# RHB0032E_pac.net
KiCad netlist of a schematic drawn in EAGLE
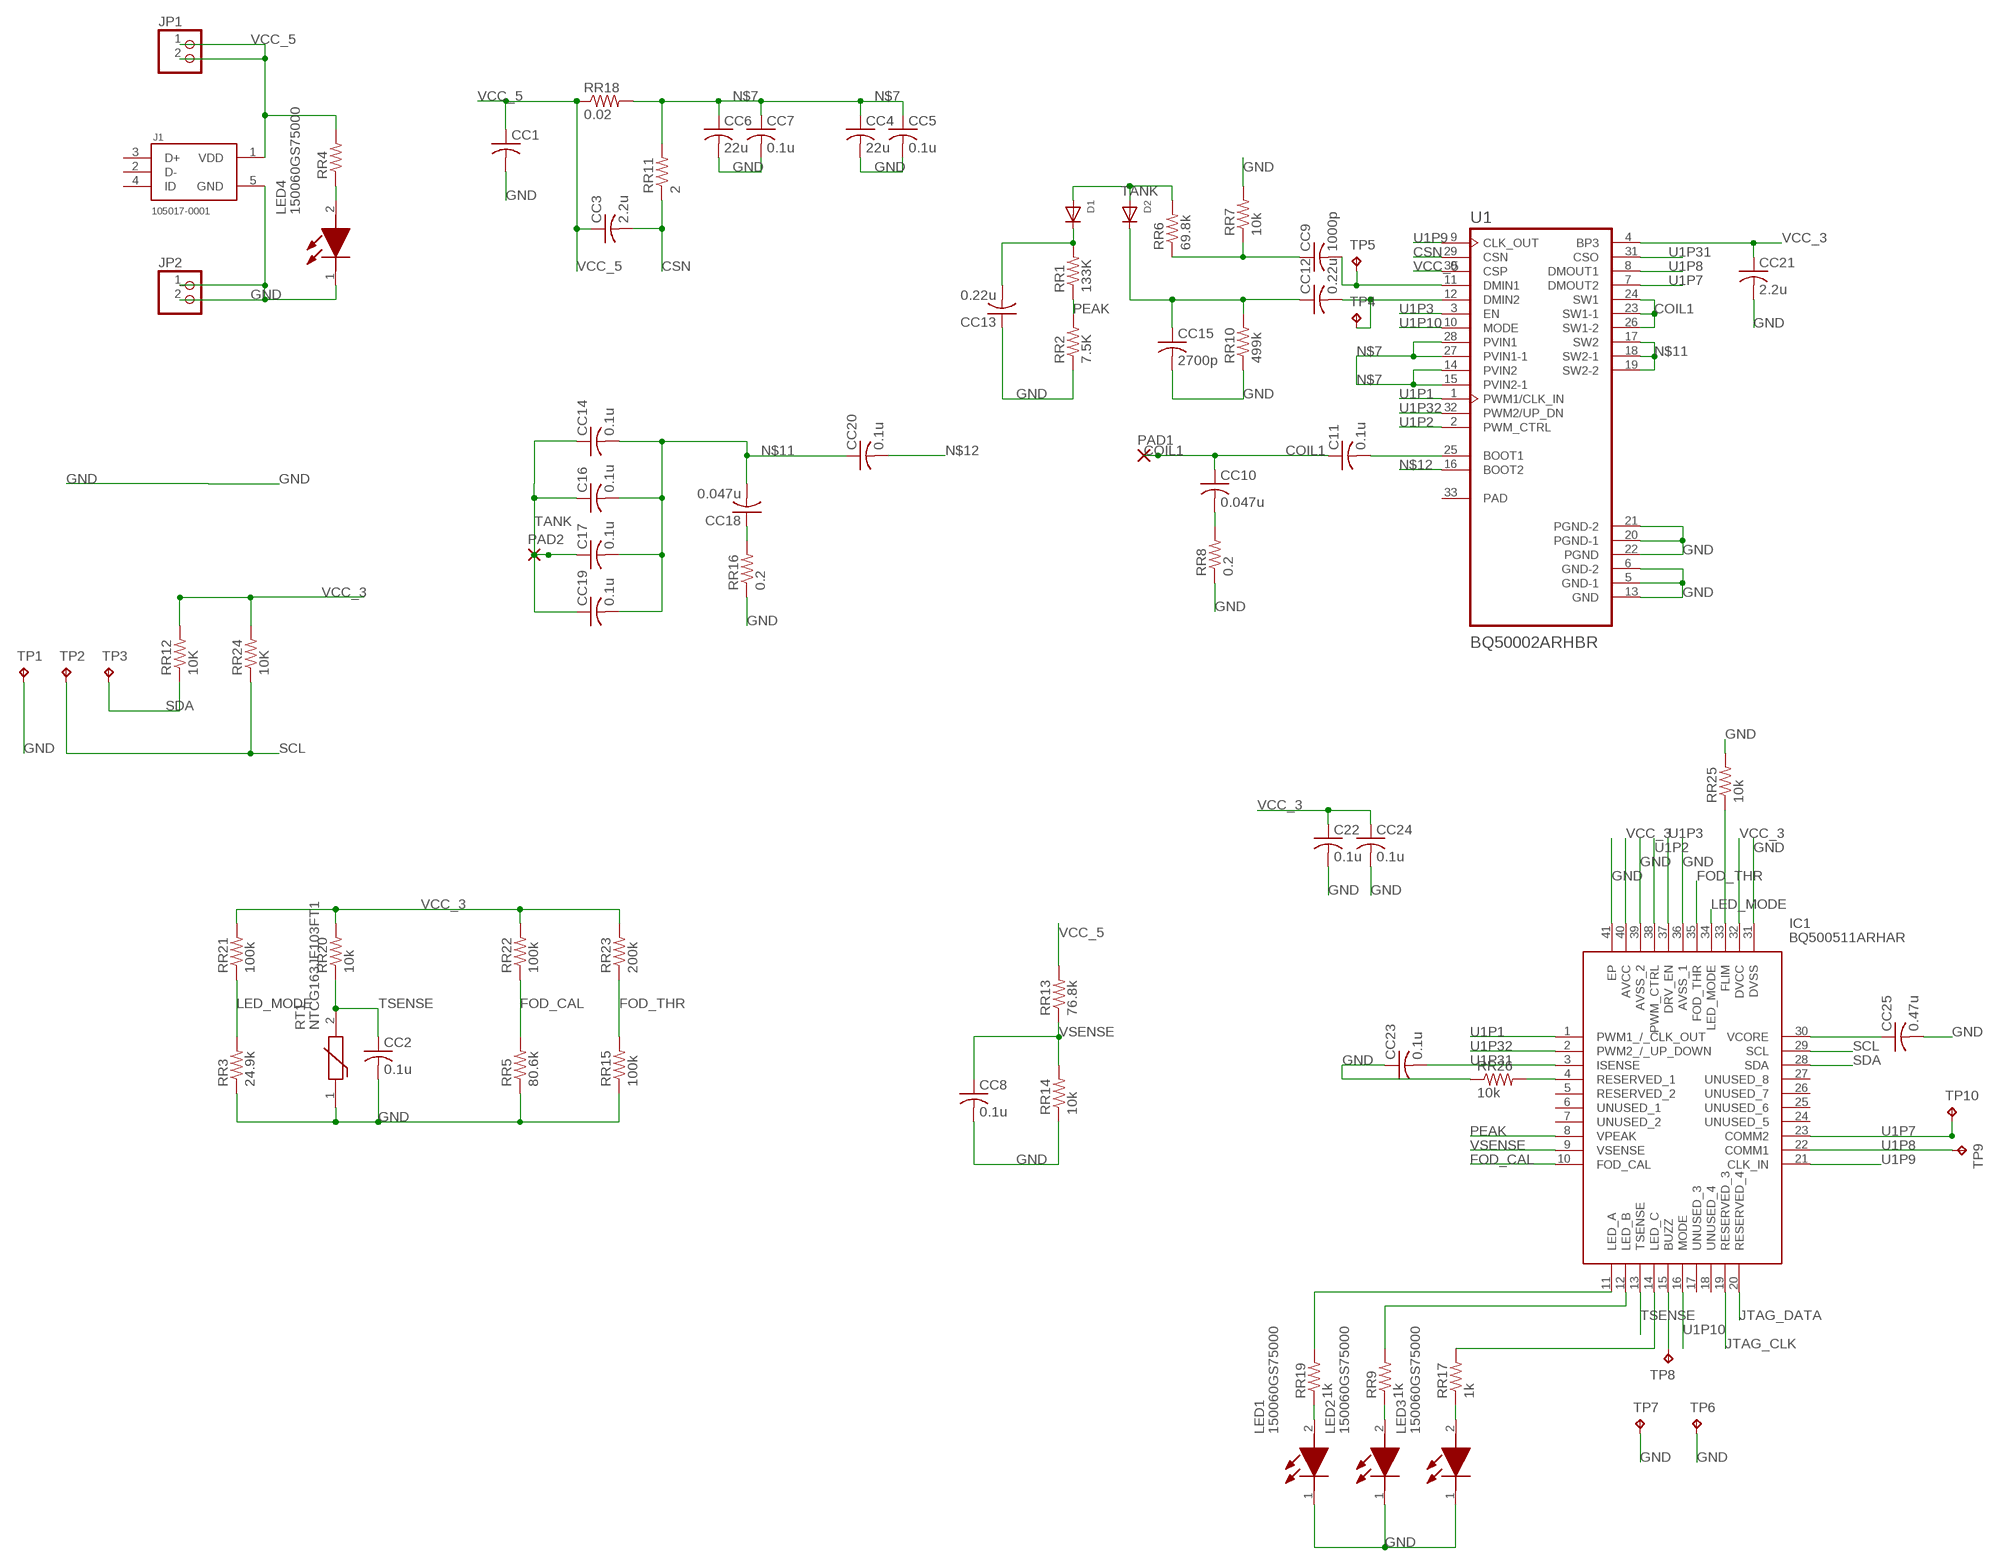
[diagram p0: schematic, sheet 1]

(export (version "E")
  (design (tool "Eeschema 10.0.6"))
  (components
    (comp (ref "C11")
      (value "0.1u")
      (footprint "eagle-import:C0402")
      (libsource (lib "eagle-import") (part "C-USC0402"))
    )
    (comp (ref "C16")
      (value "0.1u")
      (footprint "eagle-import:C0402")
      (libsource (lib "eagle-import") (part "C-USC0402"))
    )
    (comp (ref "C17")
      (value "0.1u")
      (footprint "eagle-import:C0402")
      (libsource (lib "eagle-import") (part "C-USC0402"))
    )
    (comp (ref "C22")
      (value "0.1u")
      (footprint "eagle-import:C0402")
      (libsource (lib "eagle-import") (part "C-USC0402"))
    )
    (comp (ref "CC1")
      (value "C-USC0402")
      (footprint "eagle-import:C0402")
      (libsource (lib "eagle-import") (part "C-USC0402"))
    )
    (comp (ref "CC2")
      (value "0.1u")
      (footprint "eagle-import:C0402")
      (libsource (lib "eagle-import") (part "C-USC0402"))
    )
    (comp (ref "CC3")
      (value "2.2u")
      (footprint "eagle-import:C0402")
      (libsource (lib "eagle-import") (part "C-USC0402"))
    )
    (comp (ref "CC4")
      (value "22u")
      (footprint "eagle-import:C0402")
      (libsource (lib "eagle-import") (part "C-USC0402"))
    )
    (comp (ref "CC5")
      (value "0.1u")
      (footprint "eagle-import:C0402")
      (libsource (lib "eagle-import") (part "C-USC0402"))
    )
    (comp (ref "CC6")
      (value "22u")
      (footprint "eagle-import:C0402")
      (libsource (lib "eagle-import") (part "C-USC0402"))
    )
    (comp (ref "CC7")
      (value "0.1u")
      (footprint "eagle-import:C0402")
      (libsource (lib "eagle-import") (part "C-USC0402"))
    )
    (comp (ref "CC8")
      (value "0.1u")
      (footprint "eagle-import:C0402")
      (libsource (lib "eagle-import") (part "C-USC0402"))
    )
    (comp (ref "CC9")
      (value "1000p")
      (footprint "eagle-import:C0402")
      (libsource (lib "eagle-import") (part "C-USC0402"))
    )
    (comp (ref "CC10")
      (value "0.047u")
      (footprint "eagle-import:C0402")
      (libsource (lib "eagle-import") (part "C-USC0402"))
    )
    (comp (ref "CC12")
      (value "0.22u")
      (footprint "eagle-import:C0402")
      (libsource (lib "eagle-import") (part "C-USC0402"))
    )
    (comp (ref "CC13")
      (value "0.22u")
      (footprint "eagle-import:C0402")
      (libsource (lib "eagle-import") (part "C-USC0402"))
    )
    (comp (ref "CC14")
      (value "0.1u")
      (footprint "eagle-import:C0402")
      (libsource (lib "eagle-import") (part "C-USC0402"))
    )
    (comp (ref "CC15")
      (value "2700p")
      (footprint "eagle-import:C0402")
      (libsource (lib "eagle-import") (part "C-USC0402"))
    )
    (comp (ref "CC18")
      (value "0.047u")
      (footprint "eagle-import:C0402")
      (libsource (lib "eagle-import") (part "C-USC0402"))
    )
    (comp (ref "CC19")
      (value "0.1u")
      (footprint "eagle-import:C0402")
      (libsource (lib "eagle-import") (part "C-USC0402"))
    )
    (comp (ref "CC20")
      (value "0.1u")
      (footprint "eagle-import:C0402")
      (libsource (lib "eagle-import") (part "C-USC0402"))
    )
    (comp (ref "CC21")
      (value "2.2u")
      (footprint "eagle-import:C0402")
      (libsource (lib "eagle-import") (part "C-USC0402"))
    )
    (comp (ref "CC23")
      (value "0.1u")
      (footprint "eagle-import:C0402")
      (libsource (lib "eagle-import") (part "C-USC0402"))
    )
    (comp (ref "CC24")
      (value "0.1u")
      (footprint "eagle-import:C0402")
      (libsource (lib "eagle-import") (part "C-USC0402"))
    )
    (comp (ref "CC25")
      (value "0.47u")
      (footprint "eagle-import:C0402")
      (libsource (lib "eagle-import") (part "C-USC0402"))
    )
    (comp (ref "D1")
      (value "DIODESOD-523")
      (footprint "eagle-import:SOD-523")
      (libsource (lib "eagle-import") (part "DIODESOD-523"))
    )
    (comp (ref "D2")
      (value "DIODESOD-523")
      (footprint "eagle-import:SOD-523")
      (libsource (lib "eagle-import") (part "DIODESOD-523"))
    )
    (comp (ref "IC1")
      (value "BQ500511ARHAR")
      (footprint "eagle-import:QFN50P600X600X100-41N")
      (fields (field (name "MOUSER_PART_NUMBER") "595-BQ500511ARHAR"))
      (libsource (lib "eagle-import") (part "BQ500511ARHAR"))
    )
    (comp (ref "J1")
      (value "105017-0001")
      (footprint "eagle-import:MOLEX_105017-0001")
      (fields (field (name "MF") "Molex"))
      (libsource (lib "eagle-import") (part "105017-0001"))
    )
    (comp (ref "JP1")
      (value "PINHD-1X2")
      (footprint "eagle-import:1X02")
      (libsource (lib "eagle-import") (part "PINHD-1X2"))
    )
    (comp (ref "JP2")
      (value "PINHD-1X2")
      (footprint "eagle-import:1X02")
      (libsource (lib "eagle-import") (part "PINHD-1X2"))
    )
    (comp (ref "LED1")
      (value "150060GS75000")
      (footprint "eagle-import:LEDC1608X80N")
      (fields (field (name "MOUSER_PART_NUMBER") "710-150060GS75000"))
      (libsource (lib "eagle-import") (part "150060GS75000"))
    )
    (comp (ref "LED2")
      (value "150060GS75000")
      (footprint "eagle-import:LEDC1608X80N")
      (fields (field (name "MOUSER_PART_NUMBER") "710-150060GS75000"))
      (libsource (lib "eagle-import") (part "150060GS75000"))
    )
    (comp (ref "LED3")
      (value "150060GS75000")
      (footprint "eagle-import:LEDC1608X80N")
      (fields (field (name "MOUSER_PART_NUMBER") "710-150060GS75000"))
      (libsource (lib "eagle-import") (part "150060GS75000"))
    )
    (comp (ref "LED4")
      (value "150060GS75000")
      (footprint "eagle-import:LEDC1608X80N")
      (fields (field (name "MOUSER_PART_NUMBER") "710-150060GS75000"))
      (libsource (lib "eagle-import") (part "150060GS75000"))
    )
    (comp (ref "PAD1")
      (value "SMD2")
      (footprint "eagle-import:SMD1,27-2,54")
      (libsource (lib "eagle-import") (part "SMD2"))
    )
    (comp (ref "PAD2")
      (value "SMD2")
      (footprint "eagle-import:SMD1,27-2,54")
      (libsource (lib "eagle-import") (part "SMD2"))
    )
    (comp (ref "RR1")
      (value "133K")
      (footprint "eagle-import:R0603")
      (libsource (lib "eagle-import") (part "R-US_R0603"))
    )
    (comp (ref "RR2")
      (value "7.5K")
      (footprint "eagle-import:R0603")
      (libsource (lib "eagle-import") (part "R-US_R0603"))
    )
    (comp (ref "RR3")
      (value "24.9k")
      (footprint "eagle-import:R0603")
      (libsource (lib "eagle-import") (part "R-US_R0603"))
    )
    (comp (ref "RR4")
      (value "R-US_R0603")
      (footprint "eagle-import:R0603")
      (libsource (lib "eagle-import") (part "R-US_R0603"))
    )
    (comp (ref "RR5")
      (value "80.6k")
      (footprint "eagle-import:R0603")
      (libsource (lib "eagle-import") (part "R-US_R0603"))
    )
    (comp (ref "RR6")
      (value "69.8k")
      (footprint "eagle-import:R0603")
      (libsource (lib "eagle-import") (part "R-US_R0603"))
    )
    (comp (ref "RR7")
      (value "10k")
      (footprint "eagle-import:R0603")
      (libsource (lib "eagle-import") (part "R-US_R0603"))
    )
    (comp (ref "RR8")
      (value "0.2")
      (footprint "eagle-import:R0603")
      (libsource (lib "eagle-import") (part "R-US_R0603"))
    )
    (comp (ref "RR9")
      (value "1k")
      (footprint "eagle-import:R0603")
      (libsource (lib "eagle-import") (part "R-US_R0603"))
    )
    (comp (ref "RR10")
      (value "499k")
      (footprint "eagle-import:R0603")
      (libsource (lib "eagle-import") (part "R-US_R0603"))
    )
    (comp (ref "RR11")
      (value "2")
      (footprint "eagle-import:R0603")
      (libsource (lib "eagle-import") (part "R-US_R0603"))
    )
    (comp (ref "RR12")
      (value "10K")
      (footprint "eagle-import:R0603")
      (libsource (lib "eagle-import") (part "R-US_R0603"))
    )
    (comp (ref "RR13")
      (value "76.8k")
      (footprint "eagle-import:R0603")
      (libsource (lib "eagle-import") (part "R-US_R0603"))
    )
    (comp (ref "RR14")
      (value "10k")
      (footprint "eagle-import:R0603")
      (libsource (lib "eagle-import") (part "R-US_R0603"))
    )
    (comp (ref "RR15")
      (value "100k")
      (footprint "eagle-import:R0603")
      (libsource (lib "eagle-import") (part "R-US_R0603"))
    )
    (comp (ref "RR16")
      (value "0.2")
      (footprint "eagle-import:R0603")
      (libsource (lib "eagle-import") (part "R-US_R0603"))
    )
    (comp (ref "RR17")
      (value "1k")
      (footprint "eagle-import:R0603")
      (libsource (lib "eagle-import") (part "R-US_R0603"))
    )
    (comp (ref "RR18")
      (value "0.02")
      (footprint "eagle-import:R0603")
      (libsource (lib "eagle-import") (part "R-US_R0603"))
    )
    (comp (ref "RR19")
      (value "1k")
      (footprint "eagle-import:R0603")
      (libsource (lib "eagle-import") (part "R-US_R0603"))
    )
    (comp (ref "RR20")
      (value "10k")
      (footprint "eagle-import:R0603")
      (libsource (lib "eagle-import") (part "R-US_R0603"))
    )
    (comp (ref "RR21")
      (value "100k")
      (footprint "eagle-import:R0603")
      (libsource (lib "eagle-import") (part "R-US_R0603"))
    )
    (comp (ref "RR22")
      (value "100k")
      (footprint "eagle-import:R0603")
      (libsource (lib "eagle-import") (part "R-US_R0603"))
    )
    (comp (ref "RR23")
      (value "200k")
      (footprint "eagle-import:R0603")
      (libsource (lib "eagle-import") (part "R-US_R0603"))
    )
    (comp (ref "RR24")
      (value "10K")
      (footprint "eagle-import:R0603")
      (libsource (lib "eagle-import") (part "R-US_R0603"))
    )
    (comp (ref "RR25")
      (value "10k")
      (footprint "eagle-import:R0603")
      (libsource (lib "eagle-import") (part "R-US_R0603"))
    )
    (comp (ref "RR26")
      (value "10k")
      (footprint "eagle-import:R0603")
      (libsource (lib "eagle-import") (part "R-US_R0603"))
    )
    (comp (ref "RT1")
      (value "NTCG163JF103FT1")
      (footprint "eagle-import:THRMC1608X90N")
      (fields (field (name "MOUSER_PART_NUMBER") "810-NTCG163JF103FT1"))
      (libsource (lib "eagle-import") (part "NTCG163JF103FT1"))
    )
    (comp (ref "TP1")
      (value "TPPAD1-13")
      (footprint "eagle-import:P1-13")
      (libsource (lib "eagle-import") (part "TPPAD1-13"))
    )
    (comp (ref "TP2")
      (value "TPPAD1-13")
      (footprint "eagle-import:P1-13")
      (libsource (lib "eagle-import") (part "TPPAD1-13"))
    )
    (comp (ref "TP3")
      (value "TPPAD1-13")
      (footprint "eagle-import:P1-13")
      (libsource (lib "eagle-import") (part "TPPAD1-13"))
    )
    (comp (ref "TP4")
      (value "TPPAD1-13")
      (footprint "eagle-import:P1-13")
      (libsource (lib "eagle-import") (part "TPPAD1-13"))
    )
    (comp (ref "TP5")
      (value "TPPAD1-13")
      (footprint "eagle-import:P1-13")
      (libsource (lib "eagle-import") (part "TPPAD1-13"))
    )
    (comp (ref "TP6")
      (value "TPPAD1-13")
      (footprint "eagle-import:P1-13")
      (libsource (lib "eagle-import") (part "TPPAD1-13"))
    )
    (comp (ref "TP7")
      (value "TPPAD1-13")
      (footprint "eagle-import:P1-13")
      (libsource (lib "eagle-import") (part "TPPAD1-13"))
    )
    (comp (ref "TP8")
      (value "TPPAD1-13")
      (footprint "eagle-import:P1-13")
      (libsource (lib "eagle-import") (part "TPPAD1-13"))
    )
    (comp (ref "TP9")
      (value "TPPAD1-13")
      (footprint "eagle-import:P1-13")
      (libsource (lib "eagle-import") (part "TPPAD1-13"))
    )
    (comp (ref "TP10")
      (value "TPPAD1-13")
      (footprint "eagle-import:P1-13")
      (libsource (lib "eagle-import") (part "TPPAD1-13"))
    )
    (comp (ref "U1")
      (value "BQ50002ARHBR")
      (footprint "eagle-import:IC_ADS125H01IRHBT")
      (fields (field (name "MF") "Texas Instruments"))
      (libsource (lib "eagle-import") (part "BQ50002ARHBR"))
    )
  )
  (nets
    (net (code "1") (name "/COIL1") (class "Default")
      (node (ref "C11") (pin "1") (pinfunction "1_1") (pintype "passive"))
      (node (ref "CC10") (pin "1") (pinfunction "1_1") (pintype "passive"))
      (node (ref "PAD1") (pin "1") (pinfunction "P_1") (pintype "passive"))
      (node (ref "U1") (pin "23") (pinfunction "SW1-1_23") (pintype "output"))
      (node (ref "U1") (pin "24") (pinfunction "SW1_24") (pintype "output"))
      (node (ref "U1") (pin "26") (pinfunction "SW1-2_26") (pintype "output"))
    )
    (net (code "2") (name "/CSN") (class "Default")
      (node (ref "CC3") (pin "2") (pinfunction "2_2") (pintype "passive"))
      (node (ref "RR11") (pin "1") (pinfunction "1_1") (pintype "passive"))
      (node (ref "U1") (pin "29") (pinfunction "CSN_29") (pintype "input"))
    )
    (net (code "3") (name "/FOD_CAL") (class "Default")
      (node (ref "IC1") (pin "10") (pinfunction "FOD_CAL_10") (pintype "bidirectional"))
      (node (ref "RR22") (pin "1") (pinfunction "1_1") (pintype "passive"))
      (node (ref "RR5") (pin "2") (pinfunction "2_2") (pintype "passive"))
    )
    (net (code "4") (name "/FOD_THR") (class "Default")
      (node (ref "IC1") (pin "35") (pinfunction "FOD_THR_35") (pintype "bidirectional"))
      (node (ref "RR15") (pin "2") (pinfunction "2_2") (pintype "passive"))
      (node (ref "RR23") (pin "1") (pinfunction "1_1") (pintype "passive"))
    )
    (net (code "5") (name "/GND") (class "Default")
      (node (ref "C22") (pin "2") (pinfunction "2_2") (pintype "passive"))
      (node (ref "CC1") (pin "2") (pinfunction "2_2") (pintype "passive"))
      (node (ref "CC13") (pin "1") (pinfunction "1_1") (pintype "passive"))
      (node (ref "CC15") (pin "2") (pinfunction "2_2") (pintype "passive"))
      (node (ref "CC2") (pin "2") (pinfunction "2_2") (pintype "passive"))
      (node (ref "CC21") (pin "2") (pinfunction "2_2") (pintype "passive"))
      (node (ref "CC23") (pin "1") (pinfunction "1_1") (pintype "passive"))
      (node (ref "CC24") (pin "2") (pinfunction "2_2") (pintype "passive"))
      (node (ref "CC25") (pin "2") (pinfunction "2_2") (pintype "passive"))
      (node (ref "CC4") (pin "2") (pinfunction "2_2") (pintype "passive"))
      (node (ref "CC5") (pin "2") (pinfunction "2_2") (pintype "passive"))
      (node (ref "CC6") (pin "2") (pinfunction "2_2") (pintype "passive"))
      (node (ref "CC7") (pin "2") (pinfunction "2_2") (pintype "passive"))
      (node (ref "CC8") (pin "2") (pinfunction "2_2") (pintype "passive"))
      (node (ref "IC1") (pin "31") (pinfunction "DVSS_31") (pintype "bidirectional"))
      (node (ref "IC1") (pin "36") (pinfunction "AVSS_1_36") (pintype "bidirectional"))
      (node (ref "IC1") (pin "39") (pinfunction "AVSS_2_39") (pintype "bidirectional"))
      (node (ref "IC1") (pin "41") (pinfunction "EP_41") (pintype "bidirectional"))
      (node (ref "J1") (pin "5") (pinfunction "GND_5") (pintype "power_in"))
      (node (ref "JP2") (pin "1") (pinfunction "1_1") (pintype "passive"))
      (node (ref "JP2") (pin "2") (pinfunction "2_2") (pintype "passive"))
      (node (ref "LED1") (pin "1") (pinfunction "K_1") (pintype "bidirectional"))
      (node (ref "LED2") (pin "1") (pinfunction "K_1") (pintype "bidirectional"))
      (node (ref "LED3") (pin "1") (pinfunction "K_1") (pintype "bidirectional"))
      (node (ref "LED4") (pin "1") (pinfunction "K_1") (pintype "bidirectional"))
      (node (ref "RR10") (pin "1") (pinfunction "1_1") (pintype "passive"))
      (node (ref "RR14") (pin "1") (pinfunction "1_1") (pintype "passive"))
      (node (ref "RR15") (pin "1") (pinfunction "1_1") (pintype "passive"))
      (node (ref "RR16") (pin "1") (pinfunction "1_1") (pintype "passive"))
      (node (ref "RR2") (pin "1") (pinfunction "1_1") (pintype "passive"))
      (node (ref "RR25") (pin "2") (pinfunction "2_2") (pintype "passive"))
      (node (ref "RR26") (pin "1") (pinfunction "1_1") (pintype "passive"))
      (node (ref "RR3") (pin "1") (pinfunction "1_1") (pintype "passive"))
      (node (ref "RR5") (pin "1") (pinfunction "1_1") (pintype "passive"))
      (node (ref "RR7") (pin "2") (pinfunction "2_2") (pintype "passive"))
      (node (ref "RR8") (pin "1") (pinfunction "1_1") (pintype "passive"))
      (node (ref "RT1") (pin "1") (pinfunction "1_1") (pintype "bidirectional"))
      (node (ref "TP1") (pin "TP") (pinfunction "TP_TP") (pintype "input"))
      (node (ref "TP6") (pin "TP") (pinfunction "TP_TP") (pintype "input"))
      (node (ref "TP7") (pin "TP") (pinfunction "TP_TP") (pintype "input"))
      (node (ref "U1") (pin "13") (pinfunction "GND_13") (pintype "power_in"))
      (node (ref "U1") (pin "20") (pinfunction "PGND-1_20") (pintype "power_in"))
      (node (ref "U1") (pin "21") (pinfunction "PGND-2_21") (pintype "power_in"))
      (node (ref "U1") (pin "22") (pinfunction "PGND_22") (pintype "power_in"))
      (node (ref "U1") (pin "5") (pinfunction "GND-1_5") (pintype "power_in"))
      (node (ref "U1") (pin "6") (pinfunction "GND-2_6") (pintype "power_in"))
    )
    (net (code "6") (name "/JTAG_CLK") (class "Default")
      (node (ref "IC1") (pin "19") (pinfunction "RESERVED_3_19") (pintype "bidirectional"))
    )
    (net (code "7") (name "/JTAG_DATA") (class "Default")
      (node (ref "IC1") (pin "20") (pinfunction "RESERVED_4_20") (pintype "bidirectional"))
    )
    (net (code "8") (name "/LED_MODE") (class "Default")
      (node (ref "IC1") (pin "34") (pinfunction "LED_MODE_34") (pintype "bidirectional"))
      (node (ref "RR21") (pin "1") (pinfunction "1_1") (pintype "passive"))
      (node (ref "RR3") (pin "2") (pinfunction "2_2") (pintype "passive"))
    )
    (net (code "9") (name "/N$7") (class "Default")
      (node (ref "CC4") (pin "1") (pinfunction "1_1") (pintype "passive"))
      (node (ref "CC5") (pin "1") (pinfunction "1_1") (pintype "passive"))
      (node (ref "CC6") (pin "1") (pinfunction "1_1") (pintype "passive"))
      (node (ref "CC7") (pin "1") (pinfunction "1_1") (pintype "passive"))
      (node (ref "RR11") (pin "2") (pinfunction "2_2") (pintype "passive"))
      (node (ref "RR18") (pin "2") (pinfunction "2_2") (pintype "passive"))
      (node (ref "U1") (pin "14") (pinfunction "PVIN2_14") (pintype "input"))
      (node (ref "U1") (pin "15") (pinfunction "PVIN2-1_15") (pintype "input"))
      (node (ref "U1") (pin "27") (pinfunction "PVIN1-1_27") (pintype "input"))
      (node (ref "U1") (pin "28") (pinfunction "PVIN1_28") (pintype "input"))
    )
    (net (code "10") (name "/N$11") (class "Default")
      (node (ref "C16") (pin "2") (pinfunction "2_2") (pintype "passive"))
      (node (ref "C17") (pin "2") (pinfunction "2_2") (pintype "passive"))
      (node (ref "CC14") (pin "2") (pinfunction "2_2") (pintype "passive"))
      (node (ref "CC18") (pin "2") (pinfunction "2_2") (pintype "passive"))
      (node (ref "CC19") (pin "2") (pinfunction "2_2") (pintype "passive"))
      (node (ref "CC20") (pin "1") (pinfunction "1_1") (pintype "passive"))
      (node (ref "U1") (pin "17") (pinfunction "SW2_17") (pintype "output"))
      (node (ref "U1") (pin "18") (pinfunction "SW2-1_18") (pintype "output"))
      (node (ref "U1") (pin "19") (pinfunction "SW2-2_19") (pintype "output"))
    )
    (net (code "11") (name "/N$12") (class "Default")
      (node (ref "CC20") (pin "2") (pinfunction "2_2") (pintype "passive"))
      (node (ref "U1") (pin "16") (pinfunction "BOOT2_16") (pintype "bidirectional"))
    )
    (net (code "12") (name "/PEAK") (class "Default")
      (node (ref "IC1") (pin "8") (pinfunction "VPEAK_8") (pintype "bidirectional"))
      (node (ref "RR1") (pin "1") (pinfunction "1_1") (pintype "passive"))
      (node (ref "RR2") (pin "2") (pinfunction "2_2") (pintype "passive"))
    )
    (net (code "13") (name "/SCL") (class "Default")
      (node (ref "IC1") (pin "29") (pinfunction "SCL_29") (pintype "bidirectional"))
      (node (ref "RR24") (pin "1") (pinfunction "1_1") (pintype "passive"))
      (node (ref "TP2") (pin "TP") (pinfunction "TP_TP") (pintype "input"))
    )
    (net (code "14") (name "/SDA") (class "Default")
      (node (ref "IC1") (pin "28") (pinfunction "SDA_28") (pintype "bidirectional"))
      (node (ref "RR12") (pin "1") (pinfunction "1_1") (pintype "passive"))
      (node (ref "TP3") (pin "TP") (pinfunction "TP_TP") (pintype "input"))
    )
    (net (code "15") (name "/TANK") (class "Default")
      (node (ref "C16") (pin "1") (pinfunction "1_1") (pintype "passive"))
      (node (ref "C17") (pin "1") (pinfunction "1_1") (pintype "passive"))
      (node (ref "CC14") (pin "1") (pinfunction "1_1") (pintype "passive"))
      (node (ref "CC19") (pin "1") (pinfunction "1_1") (pintype "passive"))
      (node (ref "D1") (pin "A") (pinfunction "A_A") (pintype "passive"))
      (node (ref "D2") (pin "A") (pinfunction "A_A") (pintype "passive"))
      (node (ref "PAD2") (pin "1") (pinfunction "P_1") (pintype "passive"))
      (node (ref "RR6") (pin "2") (pinfunction "2_2") (pintype "passive"))
    )
    (net (code "16") (name "/TSENSE") (class "Default")
      (node (ref "CC2") (pin "1") (pinfunction "1_1") (pintype "passive"))
      (node (ref "IC1") (pin "13") (pinfunction "TSENSE_13") (pintype "bidirectional"))
      (node (ref "RR20") (pin "1") (pinfunction "1_1") (pintype "passive"))
      (node (ref "RT1") (pin "2") (pinfunction "2_2") (pintype "bidirectional"))
    )
    (net (code "17") (name "/U1P1") (class "Default")
      (node (ref "IC1") (pin "1") (pinfunction "PWM1_/_CLK_OUT_1") (pintype "bidirectional"))
      (node (ref "U1") (pin "1") (pinfunction "PWM1/CLK_IN_1") (pintype "input"))
    )
    (net (code "18") (name "/U1P2") (class "Default")
      (node (ref "IC1") (pin "38") (pinfunction "PWM_CTRL_38") (pintype "bidirectional"))
      (node (ref "U1") (pin "2") (pinfunction "PWM_CTRL_2") (pintype "input"))
    )
    (net (code "19") (name "/U1P3") (class "Default")
      (node (ref "IC1") (pin "37") (pinfunction "DRV_EN_37") (pintype "bidirectional"))
      (node (ref "U1") (pin "3") (pinfunction "EN_3") (pintype "input"))
    )
    (net (code "20") (name "/U1P7") (class "Default")
      (node (ref "IC1") (pin "23") (pinfunction "COMM2_23") (pintype "bidirectional"))
      (node (ref "TP10") (pin "TP") (pinfunction "TP_TP") (pintype "input"))
      (node (ref "U1") (pin "7") (pinfunction "DMOUT2_7") (pintype "output"))
    )
    (net (code "21") (name "/U1P8") (class "Default")
      (node (ref "IC1") (pin "22") (pinfunction "COMM1_22") (pintype "bidirectional"))
      (node (ref "TP9") (pin "TP") (pinfunction "TP_TP") (pintype "input"))
      (node (ref "U1") (pin "8") (pinfunction "DMOUT1_8") (pintype "output"))
    )
    (net (code "22") (name "/U1P9") (class "Default")
      (node (ref "IC1") (pin "21") (pinfunction "CLK_IN_21") (pintype "bidirectional"))
      (node (ref "U1") (pin "9") (pinfunction "CLK_OUT_9") (pintype "input"))
    )
    (net (code "23") (name "/U1P10") (class "Default")
      (node (ref "IC1") (pin "16") (pinfunction "MODE_16") (pintype "bidirectional"))
      (node (ref "U1") (pin "10") (pinfunction "MODE_10") (pintype "input"))
    )
    (net (code "24") (name "/U1P31") (class "Default")
      (node (ref "CC23") (pin "2") (pinfunction "2_2") (pintype "passive"))
      (node (ref "IC1") (pin "3") (pinfunction "ISENSE_3") (pintype "bidirectional"))
      (node (ref "U1") (pin "31") (pinfunction "CSO_31") (pintype "output"))
    )
    (net (code "25") (name "/U1P32") (class "Default")
      (node (ref "IC1") (pin "2") (pinfunction "PWM2_/_UP_DOWN_2") (pintype "bidirectional"))
      (node (ref "U1") (pin "32") (pinfunction "PWM2/UP_DN_32") (pintype "input"))
    )
    (net (code "26") (name "/VCC_3") (class "Default")
      (node (ref "C22") (pin "1") (pinfunction "1_1") (pintype "passive"))
      (node (ref "CC21") (pin "1") (pinfunction "1_1") (pintype "passive"))
      (node (ref "CC24") (pin "1") (pinfunction "1_1") (pintype "passive"))
      (node (ref "IC1") (pin "32") (pinfunction "DVCC_32") (pintype "bidirectional"))
      (node (ref "IC1") (pin "40") (pinfunction "AVCC_40") (pintype "bidirectional"))
      (node (ref "RR12") (pin "2") (pinfunction "2_2") (pintype "passive"))
      (node (ref "RR20") (pin "2") (pinfunction "2_2") (pintype "passive"))
      (node (ref "RR21") (pin "2") (pinfunction "2_2") (pintype "passive"))
      (node (ref "RR22") (pin "2") (pinfunction "2_2") (pintype "passive"))
      (node (ref "RR23") (pin "2") (pinfunction "2_2") (pintype "passive"))
      (node (ref "RR24") (pin "2") (pinfunction "2_2") (pintype "passive"))
      (node (ref "U1") (pin "4") (pinfunction "BP3_4") (pintype "output"))
    )
    (net (code "27") (name "/VCC_5") (class "Default")
      (node (ref "CC1") (pin "1") (pinfunction "1_1") (pintype "passive"))
      (node (ref "CC3") (pin "1") (pinfunction "1_1") (pintype "passive"))
      (node (ref "J1") (pin "1") (pinfunction "VDD_1") (pintype "power_in"))
      (node (ref "JP1") (pin "1") (pinfunction "1_1") (pintype "passive"))
      (node (ref "JP1") (pin "2") (pinfunction "2_2") (pintype "passive"))
      (node (ref "RR13") (pin "2") (pinfunction "2_2") (pintype "passive"))
      (node (ref "RR18") (pin "1") (pinfunction "1_1") (pintype "passive"))
      (node (ref "RR4") (pin "2") (pinfunction "2_2") (pintype "passive"))
      (node (ref "U1") (pin "30") (pinfunction "CSP_30") (pintype "input"))
    )
    (net (code "28") (name "/VSENSE") (class "Default")
      (node (ref "CC8") (pin "1") (pinfunction "1_1") (pintype "passive"))
      (node (ref "IC1") (pin "9") (pinfunction "VSENSE_9") (pintype "bidirectional"))
      (node (ref "RR13") (pin "1") (pinfunction "1_1") (pintype "passive"))
      (node (ref "RR14") (pin "2") (pinfunction "2_2") (pintype "passive"))
    )
    (net (code "29") (name "Net-(CC9-Pad1)") (class "Default")
      (node (ref "CC9") (pin "1") (pinfunction "1_1") (pintype "passive"))
      (node (ref "RR6") (pin "1") (pinfunction "1_1") (pintype "passive"))
      (node (ref "RR7") (pin "1") (pinfunction "1_1") (pintype "passive"))
    )
    (net (code "30") (name "Net-(CC10-Pad2)") (class "Default")
      (node (ref "CC10") (pin "2") (pinfunction "2_2") (pintype "passive"))
      (node (ref "RR8") (pin "2") (pinfunction "2_2") (pintype "passive"))
    )
    (net (code "31") (name "Net-(CC18-Pad1)") (class "Default")
      (node (ref "CC18") (pin "1") (pinfunction "1_1") (pintype "passive"))
      (node (ref "RR16") (pin "2") (pinfunction "2_2") (pintype "passive"))
    )
    (net (code "32") (name "Net-(D1-C)") (class "Default")
      (node (ref "CC13") (pin "2") (pinfunction "2_2") (pintype "passive"))
      (node (ref "D1") (pin "K") (pinfunction "C_K") (pintype "passive"))
      (node (ref "RR1") (pin "2") (pinfunction "2_2") (pintype "passive"))
    )
    (net (code "33") (name "Net-(D2-C)") (class "Default")
      (node (ref "CC12") (pin "1") (pinfunction "1_1") (pintype "passive"))
      (node (ref "CC15") (pin "1") (pinfunction "1_1") (pintype "passive"))
      (node (ref "D2") (pin "K") (pinfunction "C_K") (pintype "passive"))
      (node (ref "RR10") (pin "2") (pinfunction "2_2") (pintype "passive"))
    )
    (net (code "34") (name "Net-(IC1-BUZZ)") (class "Default")
      (node (ref "IC1") (pin "15") (pinfunction "BUZZ_15") (pintype "bidirectional"))
      (node (ref "TP8") (pin "TP") (pinfunction "TP_TP") (pintype "input"))
    )
    (net (code "35") (name "Net-(IC1-FLIM)") (class "Default")
      (node (ref "IC1") (pin "33") (pinfunction "FLIM_33") (pintype "bidirectional"))
      (node (ref "RR25") (pin "1") (pinfunction "1_1") (pintype "passive"))
    )
    (net (code "36") (name "Net-(IC1-LED_A)") (class "Default")
      (node (ref "IC1") (pin "11") (pinfunction "LED_A_11") (pintype "bidirectional"))
      (node (ref "RR19") (pin "2") (pinfunction "2_2") (pintype "passive"))
    )
    (net (code "37") (name "Net-(IC1-LED_B)") (class "Default")
      (node (ref "IC1") (pin "12") (pinfunction "LED_B_12") (pintype "bidirectional"))
      (node (ref "RR9") (pin "2") (pinfunction "2_2") (pintype "passive"))
    )
    (net (code "38") (name "Net-(IC1-LED_C)") (class "Default")
      (node (ref "IC1") (pin "14") (pinfunction "LED_C_14") (pintype "bidirectional"))
      (node (ref "RR17") (pin "2") (pinfunction "2_2") (pintype "passive"))
    )
    (net (code "39") (name "Net-(IC1-RESERVED_1)") (class "Default")
      (node (ref "IC1") (pin "4") (pinfunction "RESERVED_1_4") (pintype "bidirectional"))
      (node (ref "RR26") (pin "2") (pinfunction "2_2") (pintype "passive"))
    )
    (net (code "40") (name "Net-(IC1-VCORE)") (class "Default")
      (node (ref "CC25") (pin "1") (pinfunction "1_1") (pintype "passive"))
      (node (ref "IC1") (pin "30") (pinfunction "VCORE_30") (pintype "bidirectional"))
    )
    (net (code "41") (name "Net-(LED1-A)") (class "Default")
      (node (ref "LED1") (pin "2") (pinfunction "A_2") (pintype "bidirectional"))
      (node (ref "RR19") (pin "1") (pinfunction "1_1") (pintype "passive"))
    )
    (net (code "42") (name "Net-(LED2-A)") (class "Default")
      (node (ref "LED2") (pin "2") (pinfunction "A_2") (pintype "bidirectional"))
      (node (ref "RR9") (pin "1") (pinfunction "1_1") (pintype "passive"))
    )
    (net (code "43") (name "Net-(LED3-A)") (class "Default")
      (node (ref "LED3") (pin "2") (pinfunction "A_2") (pintype "bidirectional"))
      (node (ref "RR17") (pin "1") (pinfunction "1_1") (pintype "passive"))
    )
    (net (code "44") (name "Net-(LED4-A)") (class "Default")
      (node (ref "LED4") (pin "2") (pinfunction "A_2") (pintype "bidirectional"))
      (node (ref "RR4") (pin "1") (pinfunction "1_1") (pintype "passive"))
    )
    (net (code "45") (name "Net-(U1-BOOT1)") (class "Default")
      (node (ref "C11") (pin "2") (pinfunction "2_2") (pintype "passive"))
      (node (ref "U1") (pin "25") (pinfunction "BOOT1_25") (pintype "bidirectional"))
    )
    (net (code "46") (name "Net-(U1-DMIN1)") (class "Default")
      (node (ref "CC9") (pin "2") (pinfunction "2_2") (pintype "passive"))
      (node (ref "TP5") (pin "TP") (pinfunction "TP_TP") (pintype "input"))
      (node (ref "U1") (pin "11") (pinfunction "DMIN1_11") (pintype "input"))
    )
    (net (code "47") (name "Net-(U1-DMIN2)") (class "Default")
      (node (ref "CC12") (pin "2") (pinfunction "2_2") (pintype "passive"))
      (node (ref "TP4") (pin "TP") (pinfunction "TP_TP") (pintype "input"))
      (node (ref "U1") (pin "12") (pinfunction "DMIN2_12") (pintype "input"))
    )
    (net (code "48") (name "unconnected-(IC1-RESERVED_2-Pad5)") (class "Default")
      (node (ref "IC1") (pin "5") (pinfunction "RESERVED_2_5") (pintype "bidirectional"))
    )
    (net (code "49") (name "unconnected-(IC1-UNUSED_1-Pad6)") (class "Default")
      (node (ref "IC1") (pin "6") (pinfunction "UNUSED_1_6") (pintype "bidirectional"))
    )
    (net (code "50") (name "unconnected-(IC1-UNUSED_2-Pad7)") (class "Default")
      (node (ref "IC1") (pin "7") (pinfunction "UNUSED_2_7") (pintype "bidirectional"))
    )
    (net (code "51") (name "unconnected-(IC1-UNUSED_3-Pad17)") (class "Default")
      (node (ref "IC1") (pin "17") (pinfunction "UNUSED_3_17") (pintype "bidirectional"))
    )
    (net (code "52") (name "unconnected-(IC1-UNUSED_4-Pad18)") (class "Default")
      (node (ref "IC1") (pin "18") (pinfunction "UNUSED_4_18") (pintype "bidirectional"))
    )
    (net (code "53") (name "unconnected-(IC1-UNUSED_5-Pad24)") (class "Default")
      (node (ref "IC1") (pin "24") (pinfunction "UNUSED_5_24") (pintype "bidirectional"))
    )
    (net (code "54") (name "unconnected-(IC1-UNUSED_6-Pad25)") (class "Default")
      (node (ref "IC1") (pin "25") (pinfunction "UNUSED_6_25") (pintype "bidirectional"))
    )
    (net (code "55") (name "unconnected-(IC1-UNUSED_7-Pad26)") (class "Default")
      (node (ref "IC1") (pin "26") (pinfunction "UNUSED_7_26") (pintype "bidirectional"))
    )
    (net (code "56") (name "unconnected-(IC1-UNUSED_8-Pad27)") (class "Default")
      (node (ref "IC1") (pin "27") (pinfunction "UNUSED_8_27") (pintype "bidirectional"))
    )
    (net (code "57") (name "unconnected-(J1-D+-Pad3)") (class "Default")
      (node (ref "J1") (pin "3") (pinfunction "D+_3") (pintype "bidirectional"))
    )
    (net (code "58") (name "unconnected-(J1-D--Pad2)") (class "Default")
      (node (ref "J1") (pin "2") (pinfunction "D-_2") (pintype "bidirectional"))
    )
    (net (code "59") (name "unconnected-(J1-ID-Pad4)") (class "Default")
      (node (ref "J1") (pin "4") (pinfunction "ID_4") (pintype "passive"))
    )
    (net (code "60") (name "unconnected-(U1-PAD-Pad33)") (class "Default")
      (node (ref "U1") (pin "33") (pinfunction "PAD_33") (pintype "bidirectional"))
    )
  )
)
